# Adafruit_SHT41.net
KiCad netlist of a schematic drawn in EAGLE
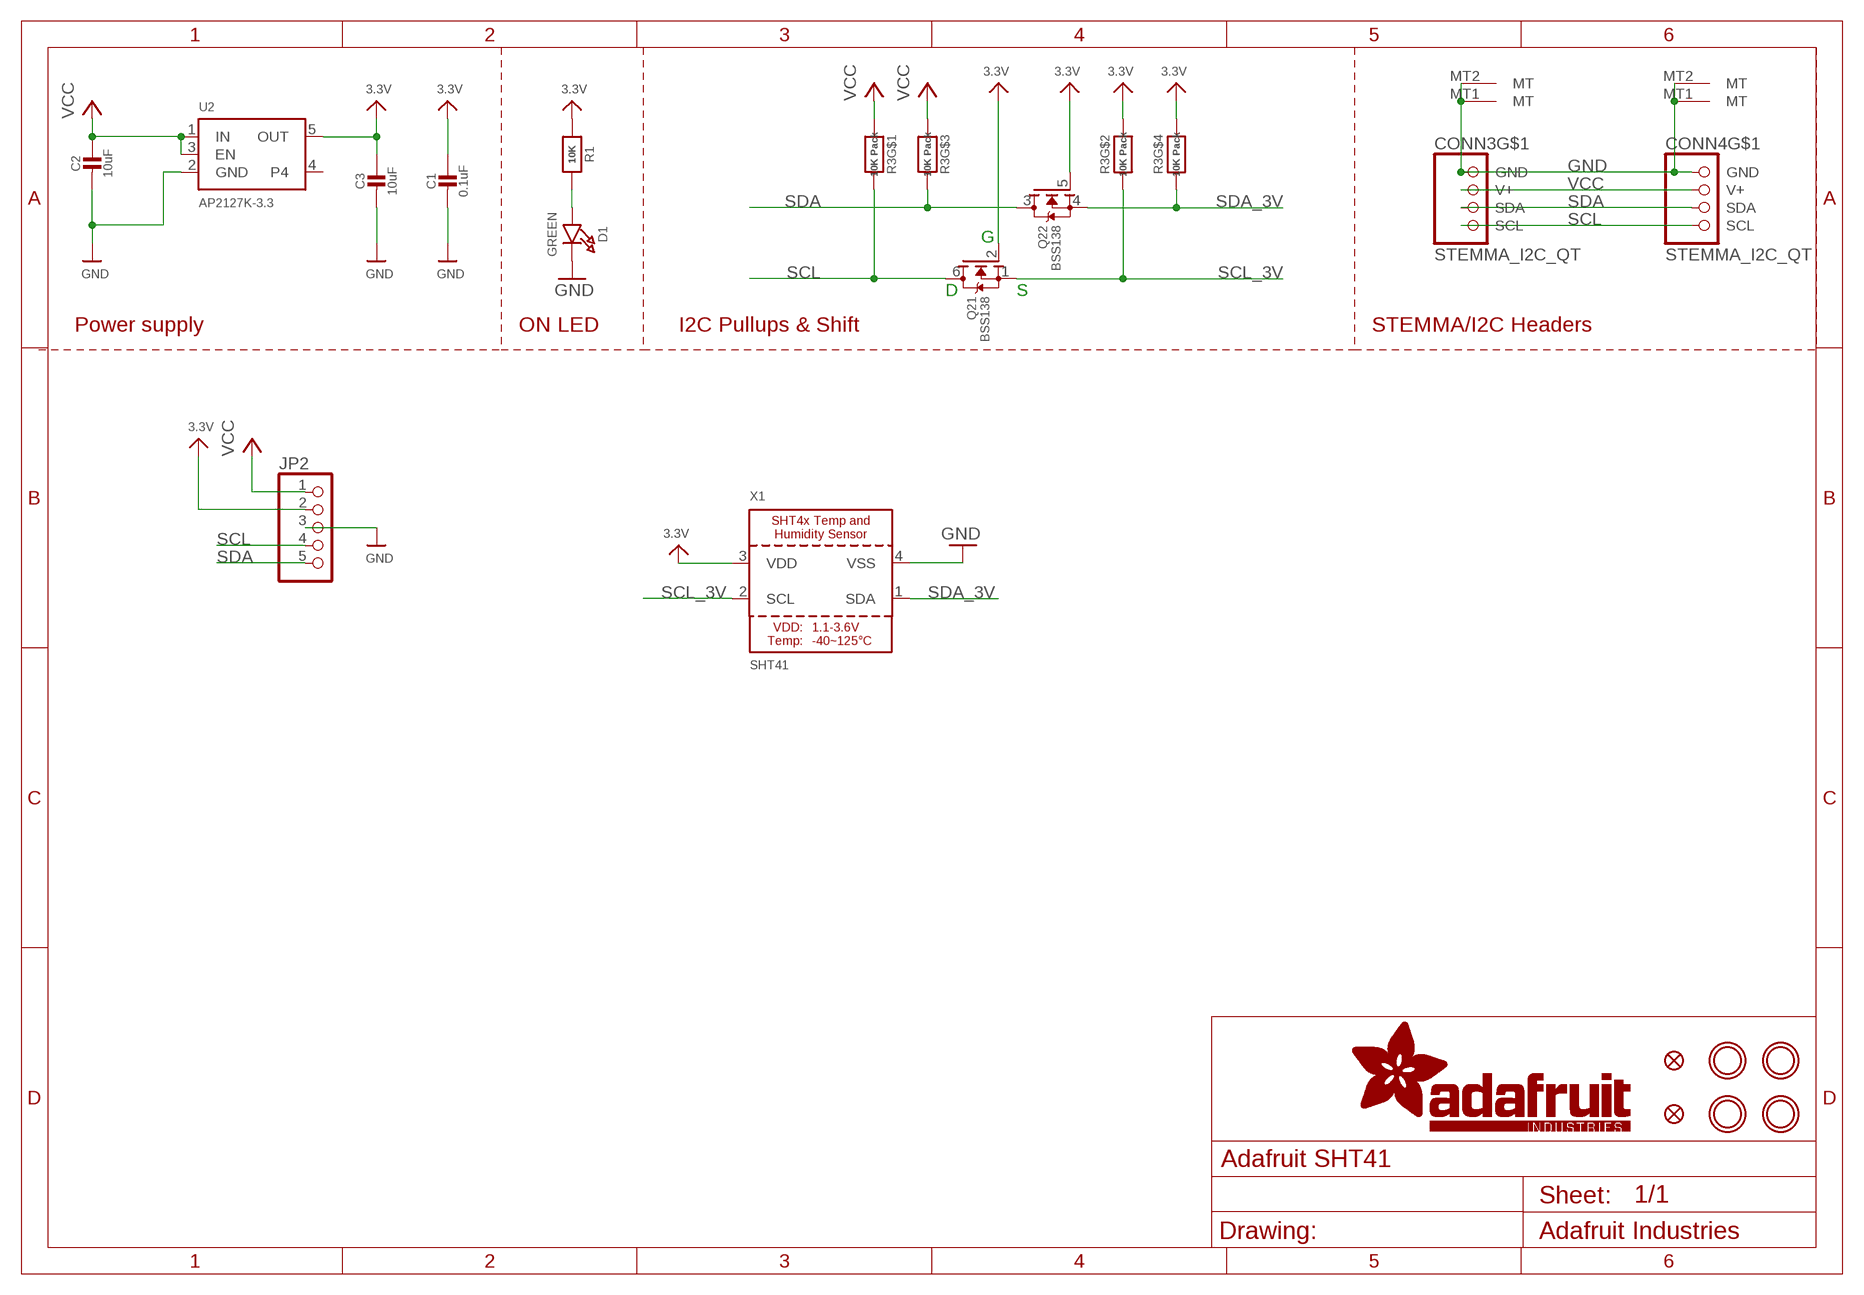
[diagram p0: schematic, sheet 1]

(export (version "E")
  (design (tool "Eeschema 10.0.6"))
  (components
    (comp (ref "C1")
      (value "0.1uF")
      (footprint "eagle-import:0603-NO")
      (libsource (lib "eagle-import") (part "CAP_CERAMIC0603_NO"))
    )
    (comp (ref "C2")
      (value "10uF")
      (footprint "eagle-import:0805-NO")
      (libsource (lib "eagle-import") (part "CAP_CERAMIC0805-NOOUTLINE"))
    )
    (comp (ref "C3")
      (value "10uF")
      (footprint "eagle-import:0805-NO")
      (libsource (lib "eagle-import") (part "CAP_CERAMIC0805-NOOUTLINE"))
    )
    (comp (ref "CONN3")
      (value "STEMMA_I2C_QT")
      (footprint "eagle-import:JST_SH4")
      (libsource (lib "eagle-import") (part "STEMMA_I2C_QT"))
    )
    (comp (ref "CONN4")
      (value "STEMMA_I2C_QT")
      (footprint "eagle-import:JST_SH4")
      (libsource (lib "eagle-import") (part "STEMMA_I2C_QT"))
    )
    (comp (ref "D1")
      (value "GREEN")
      (footprint "eagle-import:CHIPLED_0603_NOOUTLINE")
      (libsource (lib "eagle-import") (part "LED0603_NOOUTLINE"))
    )
    (comp (ref "FID3")
      (value "FIDUCIAL_1MM")
      (footprint "eagle-import:FIDUCIAL_1MM")
      (libsource (lib "eagle-import") (part "FIDUCIAL_1MM"))
    )
    (comp (ref "FID4")
      (value "FIDUCIAL_1MM")
      (footprint "eagle-import:FIDUCIAL_1MM")
      (libsource (lib "eagle-import") (part "FIDUCIAL_1MM"))
    )
    (comp (ref "JP2")
      (value "HEADER-1X570MIL")
      (footprint "eagle-import:1X05_ROUND_70")
      (libsource (lib "eagle-import") (part "HEADER-1X570MIL"))
    )
    (comp (ref "Q2")
      (value "BSS138")
      (footprint "eagle-import:SOT363")
      (libsource (lib "eagle-import") (part "MOSFET-N_DUAL"))
    )
    (comp (ref "R1")
      (value "10K")
      (footprint "eagle-import:0603-NO")
      (libsource (lib "eagle-import") (part "RESISTOR_0603_NOOUT"))
    )
    (comp (ref "R3")
      (value "10K Pack")
      (footprint "eagle-import:RESPACK_4X0603")
      (libsource (lib "eagle-import") (part "RESISTOR_4PACK"))
    )
    (comp (ref "U$1")
      (value "MOUNTINGHOLE2.5")
      (footprint "eagle-import:MOUNTINGHOLE_2.5_PLATED")
      (libsource (lib "eagle-import") (part "MOUNTINGHOLE2.5"))
    )
    (comp (ref "U$17")
      (value "MOUNTINGHOLE2.5")
      (footprint "eagle-import:MOUNTINGHOLE_2.5_PLATED")
      (libsource (lib "eagle-import") (part "MOUNTINGHOLE2.5"))
    )
    (comp (ref "U$19")
      (value "MOUNTINGHOLE2.5")
      (footprint "eagle-import:MOUNTINGHOLE_2.5_PLATED")
      (libsource (lib "eagle-import") (part "MOUNTINGHOLE2.5"))
    )
    (comp (ref "U$21")
      (value "MOUNTINGHOLE2.5")
      (footprint "eagle-import:MOUNTINGHOLE_2.5_PLATED")
      (libsource (lib "eagle-import") (part "MOUNTINGHOLE2.5"))
    )
    (comp (ref "U2")
      (value "AP2127K-3.3")
      (footprint "eagle-import:SOT23-5")
      (libsource (lib "eagle-import") (part "VREG_SOT23-5"))
    )
    (comp (ref "X1")
      (value "SHT41")
      (footprint "eagle-import:SHT4X")
      (libsource (lib "eagle-import") (part "SHT4X_"))
    )
  )
  (nets
    (net (code "1") (name "/SCL") (class "Default")
      (node (ref "CONN3") (pin "4") (pinfunction "SCL_4") (pintype "passive"))
      (node (ref "CONN4") (pin "4") (pinfunction "SCL_4") (pintype "passive"))
      (node (ref "JP2") (pin "4") (pinfunction "4_4") (pintype "passive"))
      (node (ref "Q2") (pin "6") (pinfunction "D_6") (pintype "bidirectional"))
      (node (ref "R3") (pin "8") (pinfunction "2_8") (pintype "passive"))
    )
    (net (code "2") (name "/SCL_3V") (class "Default")
      (node (ref "Q2") (pin "1") (pinfunction "S_1") (pintype "bidirectional"))
      (node (ref "R3") (pin "7") (pinfunction "2_7") (pintype "passive"))
      (node (ref "X1") (pin "2") (pinfunction "SCL_2") (pintype "bidirectional"))
    )
    (net (code "3") (name "/SDA") (class "Default")
      (node (ref "CONN3") (pin "3") (pinfunction "SDA_3") (pintype "passive"))
      (node (ref "CONN4") (pin "3") (pinfunction "SDA_3") (pintype "passive"))
      (node (ref "JP2") (pin "5") (pinfunction "5_5") (pintype "passive"))
      (node (ref "Q2") (pin "3") (pinfunction "D_3") (pintype "bidirectional"))
      (node (ref "R3") (pin "6") (pinfunction "2_6") (pintype "passive"))
    )
    (net (code "4") (name "/SDA_3V") (class "Default")
      (node (ref "Q2") (pin "4") (pinfunction "S_4") (pintype "bidirectional"))
      (node (ref "R3") (pin "5") (pinfunction "2_5") (pintype "passive"))
      (node (ref "X1") (pin "1") (pinfunction "SDA_1") (pintype "bidirectional"))
    )
    (net (code "5") (name "3.3V") (class "Default")
      (node (ref "C1") (pin "1") (pinfunction "1_1") (pintype "passive"))
      (node (ref "C3") (pin "1") (pinfunction "1_1") (pintype "passive"))
      (node (ref "JP2") (pin "2") (pinfunction "2_2") (pintype "passive"))
      (node (ref "Q2") (pin "2") (pinfunction "G_2") (pintype "bidirectional"))
      (node (ref "Q2") (pin "5") (pinfunction "G_5") (pintype "bidirectional"))
      (node (ref "R1") (pin "1") (pinfunction "1_1") (pintype "passive"))
      (node (ref "R3") (pin "2") (pinfunction "1_2") (pintype "passive"))
      (node (ref "R3") (pin "4") (pinfunction "1_4") (pintype "passive"))
      (node (ref "U2") (pin "5") (pinfunction "OUT_5") (pintype "power_in"))
      (node (ref "X1") (pin "3") (pinfunction "VDD_3") (pintype "power_in"))
    )
    (net (code "6") (name "GND") (class "Default")
      (node (ref "C1") (pin "2") (pinfunction "2_2") (pintype "passive"))
      (node (ref "C2") (pin "2") (pinfunction "2_2") (pintype "passive"))
      (node (ref "C3") (pin "2") (pinfunction "2_2") (pintype "passive"))
      (node (ref "CONN3") (pin "1") (pinfunction "GND_1") (pintype "passive"))
      (node (ref "CONN3") (pin "MT1") (pinfunction "MT_MT1") (pintype "bidirectional"))
      (node (ref "CONN3") (pin "MT2") (pinfunction "MT_MT2") (pintype "bidirectional"))
      (node (ref "CONN4") (pin "1") (pinfunction "GND_1") (pintype "passive"))
      (node (ref "CONN4") (pin "MT1") (pinfunction "MT_MT1") (pintype "bidirectional"))
      (node (ref "CONN4") (pin "MT2") (pinfunction "MT_MT2") (pintype "bidirectional"))
      (node (ref "D1") (pin "C") (pinfunction "C_C") (pintype "passive"))
      (node (ref "JP2") (pin "3") (pinfunction "3_3") (pintype "passive"))
      (node (ref "U2") (pin "2") (pinfunction "GND_2") (pintype "power_in"))
      (node (ref "X1") (pin "4") (pinfunction "VSS_4") (pintype "power_in"))
    )
    (net (code "7") (name "Net-(D1-PadA)") (class "Default")
      (node (ref "D1") (pin "A") (pinfunction "A_A") (pintype "passive"))
      (node (ref "R1") (pin "2") (pinfunction "2_2") (pintype "passive"))
    )
    (net (code "8") (name "VCC") (class "Default")
      (node (ref "C2") (pin "1") (pinfunction "1_1") (pintype "passive"))
      (node (ref "CONN3") (pin "2") (pinfunction "V+_2") (pintype "passive"))
      (node (ref "CONN4") (pin "2") (pinfunction "V+_2") (pintype "passive"))
      (node (ref "JP2") (pin "1") (pinfunction "1_1") (pintype "passive"))
      (node (ref "R3") (pin "1") (pinfunction "1_1") (pintype "passive"))
      (node (ref "R3") (pin "3") (pinfunction "1_3") (pintype "passive"))
      (node (ref "U2") (pin "1") (pinfunction "IN_1") (pintype "power_in"))
      (node (ref "U2") (pin "3") (pinfunction "EN_3") (pintype "input"))
    )
    (net (code "9") (name "unconnected-(U2-P4-Pad4)") (class "Default")
      (node (ref "U2") (pin "4") (pinfunction "P4_4") (pintype "bidirectional"))
    )
  )
)
